# PlusCart.net
KiCad netlist of a schematic drawn in EAGLE
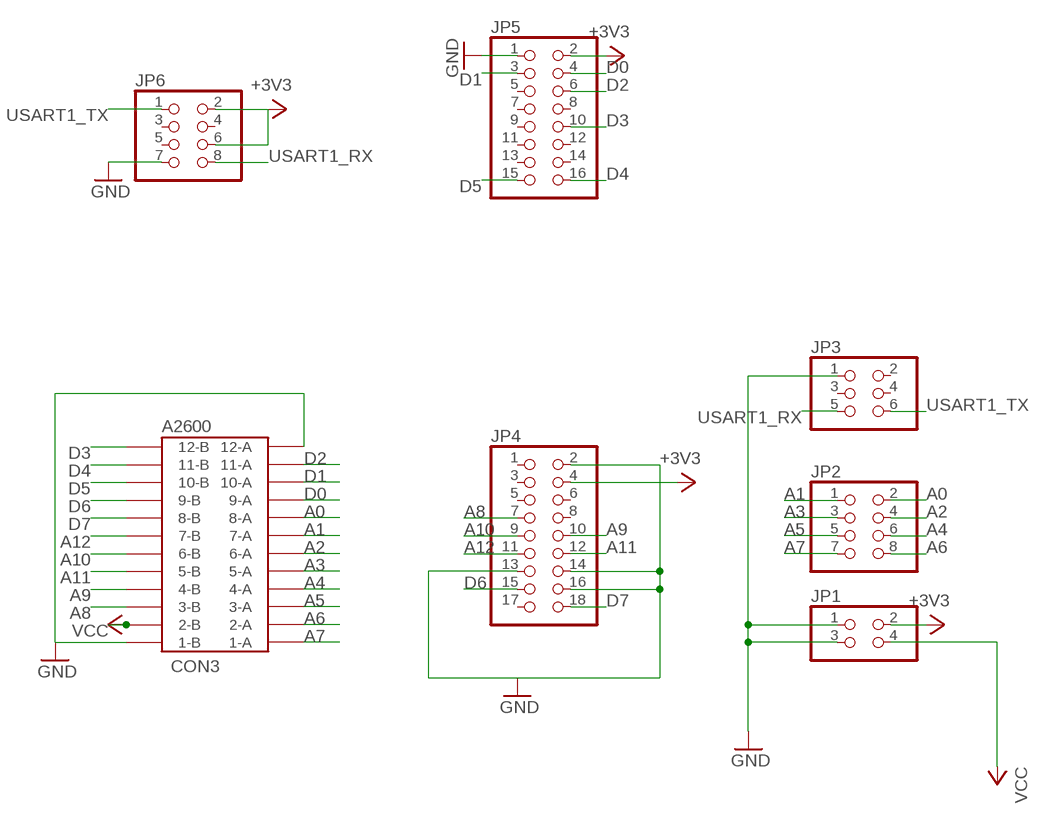
[diagram p0: schematic, sheet 1]

(export (version "E")
  (design (tool "Eeschema 10.0.6"))
  (components
    (comp (ref "CON3")
      (value "A2600")
      (footprint "eagle-import:24PINEDGE-254MM")
      (libsource (lib "eagle-import") (part "24PINEDGE-254MM"))
    )
    (comp (ref "JP1")
      (value "PINHD-2X2")
      (footprint "eagle-import:2X02")
      (libsource (lib "eagle-import") (part "PINHD-2X2"))
    )
    (comp (ref "JP2")
      (value "PINHD-2X4")
      (footprint "eagle-import:2X04")
      (libsource (lib "eagle-import") (part "PINHD-2X4"))
    )
    (comp (ref "JP3")
      (value "PINHD-2X3")
      (footprint "eagle-import:2X03")
      (libsource (lib "eagle-import") (part "PINHD-2X3"))
    )
    (comp (ref "JP4")
      (value "PINHD-2X9")
      (footprint "eagle-import:2X09")
      (libsource (lib "eagle-import") (part "PINHD-2X9"))
    )
    (comp (ref "JP5")
      (value "PINHD-2X8")
      (footprint "eagle-import:2X08")
      (libsource (lib "eagle-import") (part "PINHD-2X8"))
    )
    (comp (ref "JP6")
      (value "PINHD-2X4")
      (footprint "eagle-import:2X04")
      (libsource (lib "eagle-import") (part "PINHD-2X4"))
    )
  )
  (nets
    (net (code "1") (name "+3V3") (class "Default")
      (node (ref "JP1") (pin "2") (pinfunction "2_2") (pintype "passive"))
      (node (ref "JP4") (pin "4") (pinfunction "4_4") (pintype "passive"))
      (node (ref "JP5") (pin "2") (pinfunction "2_2") (pintype "passive"))
      (node (ref "JP6") (pin "2") (pinfunction "2_2") (pintype "passive"))
      (node (ref "JP6") (pin "6") (pinfunction "6_6") (pintype "passive"))
    )
    (net (code "2") (name "/A0") (class "Default")
      (node (ref "CON3") (pin "8-A") (pinfunction "8-A_8-A") (pintype "passive"))
      (node (ref "JP2") (pin "2") (pinfunction "2_2") (pintype "passive"))
    )
    (net (code "3") (name "/A1") (class "Default")
      (node (ref "CON3") (pin "7-A") (pinfunction "7-A_7-A") (pintype "passive"))
      (node (ref "JP2") (pin "1") (pinfunction "1_1") (pintype "passive"))
    )
    (net (code "4") (name "/A2") (class "Default")
      (node (ref "CON3") (pin "6-A") (pinfunction "6-A_6-A") (pintype "passive"))
      (node (ref "JP2") (pin "4") (pinfunction "4_4") (pintype "passive"))
    )
    (net (code "5") (name "/A3") (class "Default")
      (node (ref "CON3") (pin "5-A") (pinfunction "5-A_5-A") (pintype "passive"))
      (node (ref "JP2") (pin "3") (pinfunction "3_3") (pintype "passive"))
    )
    (net (code "6") (name "/A4") (class "Default")
      (node (ref "CON3") (pin "4-A") (pinfunction "4-A_4-A") (pintype "passive"))
      (node (ref "JP2") (pin "6") (pinfunction "6_6") (pintype "passive"))
    )
    (net (code "7") (name "/A5") (class "Default")
      (node (ref "CON3") (pin "3-A") (pinfunction "3-A_3-A") (pintype "passive"))
      (node (ref "JP2") (pin "5") (pinfunction "5_5") (pintype "passive"))
    )
    (net (code "8") (name "/A6") (class "Default")
      (node (ref "CON3") (pin "2-A") (pinfunction "2-A_2-A") (pintype "passive"))
      (node (ref "JP2") (pin "8") (pinfunction "8_8") (pintype "passive"))
    )
    (net (code "9") (name "/A7") (class "Default")
      (node (ref "CON3") (pin "1-A") (pinfunction "1-A_1-A") (pintype "passive"))
      (node (ref "JP2") (pin "7") (pinfunction "7_7") (pintype "passive"))
    )
    (net (code "10") (name "/A8") (class "Default")
      (node (ref "CON3") (pin "3-B") (pinfunction "3-B_3-B") (pintype "passive"))
      (node (ref "JP4") (pin "7") (pinfunction "7_7") (pintype "passive"))
    )
    (net (code "11") (name "/A9") (class "Default")
      (node (ref "CON3") (pin "4-B") (pinfunction "4-B_4-B") (pintype "passive"))
      (node (ref "JP4") (pin "10") (pinfunction "10_10") (pintype "passive"))
    )
    (net (code "12") (name "/A10") (class "Default")
      (node (ref "CON3") (pin "6-B") (pinfunction "6-B_6-B") (pintype "passive"))
      (node (ref "JP4") (pin "9") (pinfunction "9_9") (pintype "passive"))
    )
    (net (code "13") (name "/A11") (class "Default")
      (node (ref "CON3") (pin "5-B") (pinfunction "5-B_5-B") (pintype "passive"))
      (node (ref "JP4") (pin "12") (pinfunction "12_12") (pintype "passive"))
    )
    (net (code "14") (name "/A12") (class "Default")
      (node (ref "CON3") (pin "7-B") (pinfunction "7-B_7-B") (pintype "passive"))
      (node (ref "JP4") (pin "11") (pinfunction "11_11") (pintype "passive"))
    )
    (net (code "15") (name "/D0") (class "Default")
      (node (ref "CON3") (pin "9-A") (pinfunction "9-A_9-A") (pintype "passive"))
      (node (ref "JP5") (pin "4") (pinfunction "4_4") (pintype "passive"))
    )
    (net (code "16") (name "/D1") (class "Default")
      (node (ref "CON3") (pin "10-A") (pinfunction "10-A_10-A") (pintype "passive"))
      (node (ref "JP5") (pin "3") (pinfunction "3_3") (pintype "passive"))
    )
    (net (code "17") (name "/D2") (class "Default")
      (node (ref "CON3") (pin "11-A") (pinfunction "11-A_11-A") (pintype "passive"))
      (node (ref "JP5") (pin "6") (pinfunction "6_6") (pintype "passive"))
    )
    (net (code "18") (name "/D3") (class "Default")
      (node (ref "CON3") (pin "12-B") (pinfunction "12-B_12-B") (pintype "passive"))
      (node (ref "JP5") (pin "10") (pinfunction "10_10") (pintype "passive"))
    )
    (net (code "19") (name "/D4") (class "Default")
      (node (ref "CON3") (pin "11-B") (pinfunction "11-B_11-B") (pintype "passive"))
      (node (ref "JP5") (pin "16") (pinfunction "16_16") (pintype "passive"))
    )
    (net (code "20") (name "/D5") (class "Default")
      (node (ref "CON3") (pin "10-B") (pinfunction "10-B_10-B") (pintype "passive"))
      (node (ref "JP5") (pin "15") (pinfunction "15_15") (pintype "passive"))
    )
    (net (code "21") (name "/D6") (class "Default")
      (node (ref "CON3") (pin "9-B") (pinfunction "9-B_9-B") (pintype "passive"))
      (node (ref "JP4") (pin "15") (pinfunction "15_15") (pintype "passive"))
    )
    (net (code "22") (name "/D7") (class "Default")
      (node (ref "CON3") (pin "8-B") (pinfunction "8-B_8-B") (pintype "passive"))
      (node (ref "JP4") (pin "18") (pinfunction "18_18") (pintype "passive"))
    )
    (net (code "23") (name "/USART1_RX") (class "Default")
      (node (ref "JP3") (pin "5") (pinfunction "5_5") (pintype "passive"))
      (node (ref "JP6") (pin "8") (pinfunction "8_8") (pintype "passive"))
    )
    (net (code "24") (name "/USART1_TX") (class "Default")
      (node (ref "JP3") (pin "6") (pinfunction "6_6") (pintype "passive"))
      (node (ref "JP6") (pin "1") (pinfunction "1_1") (pintype "passive"))
    )
    (net (code "25") (name "GND") (class "Default")
      (node (ref "CON3") (pin "1-B") (pinfunction "1-B_1-B") (pintype "passive"))
      (node (ref "CON3") (pin "12-A") (pinfunction "12-A_12-A") (pintype "passive"))
      (node (ref "JP1") (pin "1") (pinfunction "1_1") (pintype "passive"))
      (node (ref "JP1") (pin "3") (pinfunction "3_3") (pintype "passive"))
      (node (ref "JP3") (pin "1") (pinfunction "1_1") (pintype "passive"))
      (node (ref "JP4") (pin "13") (pinfunction "13_13") (pintype "passive"))
      (node (ref "JP4") (pin "14") (pinfunction "14_14") (pintype "passive"))
      (node (ref "JP4") (pin "16") (pinfunction "16_16") (pintype "passive"))
      (node (ref "JP4") (pin "2") (pinfunction "2_2") (pintype "passive"))
      (node (ref "JP5") (pin "1") (pinfunction "1_1") (pintype "passive"))
      (node (ref "JP6") (pin "7") (pinfunction "7_7") (pintype "passive"))
    )
    (net (code "26") (name "VCC") (class "Default")
      (node (ref "CON3") (pin "2-B") (pinfunction "2-B_2-B") (pintype "passive"))
      (node (ref "JP1") (pin "4") (pinfunction "4_4") (pintype "passive"))
    )
    (net (code "27") (name "unconnected-(JP3-Pad2)") (class "Default")
      (node (ref "JP3") (pin "2") (pinfunction "2_2") (pintype "passive"))
    )
    (net (code "28") (name "unconnected-(JP3-Pad3)") (class "Default")
      (node (ref "JP3") (pin "3") (pinfunction "3_3") (pintype "passive"))
    )
    (net (code "29") (name "unconnected-(JP3-Pad4)") (class "Default")
      (node (ref "JP3") (pin "4") (pinfunction "4_4") (pintype "passive"))
    )
    (net (code "30") (name "unconnected-(JP4-Pad1)") (class "Default")
      (node (ref "JP4") (pin "1") (pinfunction "1_1") (pintype "passive"))
    )
    (net (code "31") (name "unconnected-(JP4-Pad3)") (class "Default")
      (node (ref "JP4") (pin "3") (pinfunction "3_3") (pintype "passive"))
    )
    (net (code "32") (name "unconnected-(JP4-Pad5)") (class "Default")
      (node (ref "JP4") (pin "5") (pinfunction "5_5") (pintype "passive"))
    )
    (net (code "33") (name "unconnected-(JP4-Pad6)") (class "Default")
      (node (ref "JP4") (pin "6") (pinfunction "6_6") (pintype "passive"))
    )
    (net (code "34") (name "unconnected-(JP4-Pad8)") (class "Default")
      (node (ref "JP4") (pin "8") (pinfunction "8_8") (pintype "passive"))
    )
    (net (code "35") (name "unconnected-(JP4-Pad17)") (class "Default")
      (node (ref "JP4") (pin "17") (pinfunction "17_17") (pintype "passive"))
    )
    (net (code "36") (name "unconnected-(JP5-Pad5)") (class "Default")
      (node (ref "JP5") (pin "5") (pinfunction "5_5") (pintype "passive"))
    )
    (net (code "37") (name "unconnected-(JP5-Pad7)") (class "Default")
      (node (ref "JP5") (pin "7") (pinfunction "7_7") (pintype "passive"))
    )
    (net (code "38") (name "unconnected-(JP5-Pad8)") (class "Default")
      (node (ref "JP5") (pin "8") (pinfunction "8_8") (pintype "passive"))
    )
    (net (code "39") (name "unconnected-(JP5-Pad9)") (class "Default")
      (node (ref "JP5") (pin "9") (pinfunction "9_9") (pintype "passive"))
    )
    (net (code "40") (name "unconnected-(JP5-Pad11)") (class "Default")
      (node (ref "JP5") (pin "11") (pinfunction "11_11") (pintype "passive"))
    )
    (net (code "41") (name "unconnected-(JP5-Pad12)") (class "Default")
      (node (ref "JP5") (pin "12") (pinfunction "12_12") (pintype "passive"))
    )
    (net (code "42") (name "unconnected-(JP5-Pad13)") (class "Default")
      (node (ref "JP5") (pin "13") (pinfunction "13_13") (pintype "passive"))
    )
    (net (code "43") (name "unconnected-(JP5-Pad14)") (class "Default")
      (node (ref "JP5") (pin "14") (pinfunction "14_14") (pintype "passive"))
    )
    (net (code "44") (name "unconnected-(JP6-Pad3)") (class "Default")
      (node (ref "JP6") (pin "3") (pinfunction "3_3") (pintype "passive"))
    )
    (net (code "45") (name "unconnected-(JP6-Pad4)") (class "Default")
      (node (ref "JP6") (pin "4") (pinfunction "4_4") (pintype "passive"))
    )
    (net (code "46") (name "unconnected-(JP6-Pad5)") (class "Default")
      (node (ref "JP6") (pin "5") (pinfunction "5_5") (pintype "passive"))
    )
  )
)
